# p-mos_breakout.net
KiCad netlist of a schematic drawn in EAGLE
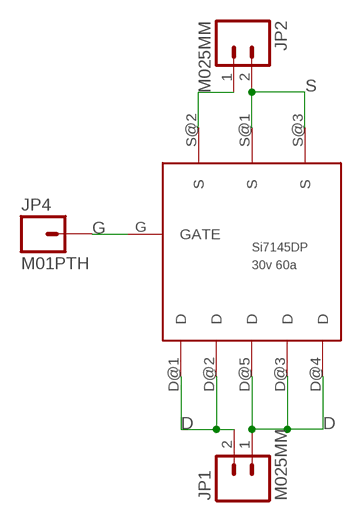
[diagram p0: schematic, sheet 1]

(export (version "E")
  (design (tool "Eeschema 10.0.6"))
  (components
    (comp (ref "JP1")
      (value "M025MM")
      (footprint "eagle-import:SCREWTERMINAL-5MM-2")
      (libsource (lib "eagle-import") (part "M025MM"))
    )
    (comp (ref "JP2")
      (value "M025MM")
      (footprint "eagle-import:SCREWTERMINAL-5MM-2")
      (libsource (lib "eagle-import") (part "M025MM"))
    )
    (comp (ref "JP4")
      (value "M01PTH")
      (footprint "eagle-import:1X01")
      (libsource (lib "eagle-import") (part "M01PTH"))
    )
    (comp (ref "U$1")
      (value "PMOS-SI7145DP")
      (footprint "eagle-import:S0-8")
      (libsource (lib "eagle-import") (part "PMOS-SI7145DP"))
    )
  )
  (nets
    (net (code "1") (name "/D") (class "Default")
      (node (ref "JP1") (pin "1") (pinfunction "1_1") (pintype "passive"))
      (node (ref "JP1") (pin "2") (pinfunction "2_2") (pintype "passive"))
      (node (ref "U$1") (pin "D@1") (pinfunction "D_D@1") (pintype "output"))
      (node (ref "U$1") (pin "D@2") (pinfunction "D_D@2") (pintype "output"))
      (node (ref "U$1") (pin "D@3") (pinfunction "D_D@3") (pintype "output"))
      (node (ref "U$1") (pin "D@4") (pinfunction "D_D@4") (pintype "output"))
      (node (ref "U$1") (pin "D@5") (pinfunction "D_D@5") (pintype "output"))
    )
    (net (code "2") (name "/G") (class "Default")
      (node (ref "JP4") (pin "1") (pinfunction "1_1") (pintype "passive"))
      (node (ref "U$1") (pin "G") (pinfunction "GATE_G") (pintype "input"))
    )
    (net (code "3") (name "/S") (class "Default")
      (node (ref "JP2") (pin "1") (pinfunction "1_1") (pintype "passive"))
      (node (ref "JP2") (pin "2") (pinfunction "2_2") (pintype "passive"))
      (node (ref "U$1") (pin "S@1") (pinfunction "S_S@1") (pintype "input"))
      (node (ref "U$1") (pin "S@2") (pinfunction "S_S@2") (pintype "input"))
      (node (ref "U$1") (pin "S@3") (pinfunction "S_S@3") (pintype "input"))
    )
  )
)
